# Sheet1.net
KiCad netlist of a schematic drawn in Altium Designer
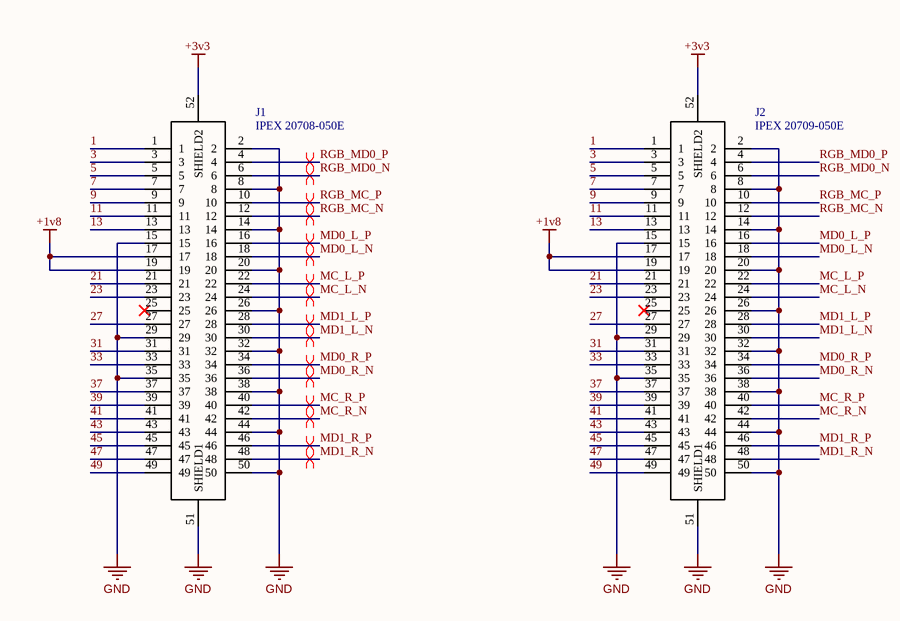
[diagram p0: Sheet1.SchDoc]

(export (version "E")
  (design (tool "Eeschema 10.0.6"))
  (components
    (comp (ref "J1")
      (value "IPEX 20708-050E")
      (footprint "IPEX_20708-050E-01")
      (description "50-Pin Plug. Mates with 20709-050E.")
      (libsource (lib "Schlib1") (part "NOVASTACK 35-P 50 Pin Plug"))
    )
    (comp (ref "J2")
      (value "IPEX 20709-050E")
      (footprint "IPEX_20709-050E-01_20709-050E-01(Primary)")
      (description "50-Pin Plug. Mates with 20708-050E.")
      (libsource (lib "Schlib1") (part "NOVASTACK 35-P 50 Pin Receptical"))
    )
  )
  (nets
    (net (code "1") (name "+1v8") (class "Default")
      (node (ref "J1") (pin "17") (pinfunction "17_17") (pintype "passive"))
      (node (ref "J1") (pin "19") (pinfunction "19_19") (pintype "passive"))
      (node (ref "J2") (pin "17") (pinfunction "17_17") (pintype "passive"))
      (node (ref "J2") (pin "19") (pinfunction "19_19") (pintype "passive"))
    )
    (net (code "2") (name "+3v3") (class "Default")
      (node (ref "J1") (pin "52") (pinfunction "SHIELD2_52") (pintype "passive"))
      (node (ref "J2") (pin "52") (pinfunction "SHIELD2_52") (pintype "passive"))
    )
    (net (code "3") (name "/1") (class "Default")
      (node (ref "J1") (pin "1") (pinfunction "1_1") (pintype "passive"))
      (node (ref "J2") (pin "1") (pinfunction "1_1") (pintype "passive"))
    )
    (net (code "4") (name "/3") (class "Default")
      (node (ref "J1") (pin "3") (pinfunction "3_3") (pintype "passive"))
      (node (ref "J2") (pin "3") (pinfunction "3_3") (pintype "passive"))
    )
    (net (code "5") (name "/5") (class "Default")
      (node (ref "J1") (pin "5") (pinfunction "5_5") (pintype "passive"))
      (node (ref "J2") (pin "5") (pinfunction "5_5") (pintype "passive"))
    )
    (net (code "6") (name "/7") (class "Default")
      (node (ref "J1") (pin "7") (pinfunction "7_7") (pintype "passive"))
      (node (ref "J2") (pin "7") (pinfunction "7_7") (pintype "passive"))
    )
    (net (code "7") (name "/9") (class "Default")
      (node (ref "J1") (pin "9") (pinfunction "9_9") (pintype "passive"))
      (node (ref "J2") (pin "9") (pinfunction "9_9") (pintype "passive"))
    )
    (net (code "8") (name "/11") (class "Default")
      (node (ref "J1") (pin "11") (pinfunction "11_11") (pintype "passive"))
      (node (ref "J2") (pin "11") (pinfunction "11_11") (pintype "passive"))
    )
    (net (code "9") (name "/13") (class "Default")
      (node (ref "J1") (pin "13") (pinfunction "13_13") (pintype "passive"))
      (node (ref "J2") (pin "13") (pinfunction "13_13") (pintype "passive"))
    )
    (net (code "10") (name "/21") (class "Default")
      (node (ref "J1") (pin "21") (pinfunction "21_21") (pintype "passive"))
      (node (ref "J2") (pin "21") (pinfunction "21_21") (pintype "passive"))
    )
    (net (code "11") (name "/23") (class "Default")
      (node (ref "J1") (pin "23") (pinfunction "23_23") (pintype "passive"))
      (node (ref "J2") (pin "23") (pinfunction "23_23") (pintype "passive"))
    )
    (net (code "12") (name "/27") (class "Default")
      (node (ref "J1") (pin "27") (pinfunction "27_27") (pintype "passive"))
      (node (ref "J2") (pin "27") (pinfunction "27_27") (pintype "passive"))
    )
    (net (code "13") (name "/31") (class "Default")
      (node (ref "J1") (pin "31") (pinfunction "31_31") (pintype "passive"))
      (node (ref "J2") (pin "31") (pinfunction "31_31") (pintype "passive"))
    )
    (net (code "14") (name "/33") (class "Default")
      (node (ref "J1") (pin "33") (pinfunction "33_33") (pintype "passive"))
      (node (ref "J2") (pin "33") (pinfunction "33_33") (pintype "passive"))
    )
    (net (code "15") (name "/37") (class "Default")
      (node (ref "J1") (pin "37") (pinfunction "37_37") (pintype "passive"))
      (node (ref "J2") (pin "37") (pinfunction "37_37") (pintype "passive"))
    )
    (net (code "16") (name "/39") (class "Default")
      (node (ref "J1") (pin "39") (pinfunction "39_39") (pintype "passive"))
      (node (ref "J2") (pin "39") (pinfunction "39_39") (pintype "passive"))
    )
    (net (code "17") (name "/41") (class "Default")
      (node (ref "J1") (pin "41") (pinfunction "41_41") (pintype "passive"))
      (node (ref "J2") (pin "41") (pinfunction "41_41") (pintype "passive"))
    )
    (net (code "18") (name "/43") (class "Default")
      (node (ref "J1") (pin "43") (pinfunction "43_43") (pintype "passive"))
      (node (ref "J2") (pin "43") (pinfunction "43_43") (pintype "passive"))
    )
    (net (code "19") (name "/45") (class "Default")
      (node (ref "J1") (pin "45") (pinfunction "45_45") (pintype "passive"))
      (node (ref "J2") (pin "45") (pinfunction "45_45") (pintype "passive"))
    )
    (net (code "20") (name "/47") (class "Default")
      (node (ref "J1") (pin "47") (pinfunction "47_47") (pintype "passive"))
      (node (ref "J2") (pin "47") (pinfunction "47_47") (pintype "passive"))
    )
    (net (code "21") (name "/49") (class "Default")
      (node (ref "J1") (pin "49") (pinfunction "49_49") (pintype "passive"))
      (node (ref "J2") (pin "49") (pinfunction "49_49") (pintype "passive"))
    )
    (net (code "22") (name "/MC_L_N") (class "Default")
      (node (ref "J1") (pin "24") (pinfunction "24_24") (pintype "passive"))
      (node (ref "J2") (pin "24") (pinfunction "24_24") (pintype "passive"))
    )
    (net (code "23") (name "/MC_L_P") (class "Default")
      (node (ref "J1") (pin "22") (pinfunction "22_22") (pintype "passive"))
      (node (ref "J2") (pin "22") (pinfunction "22_22") (pintype "passive"))
    )
    (net (code "24") (name "/MC_R_N") (class "Default")
      (node (ref "J1") (pin "42") (pinfunction "42_42") (pintype "passive"))
      (node (ref "J2") (pin "42") (pinfunction "42_42") (pintype "passive"))
    )
    (net (code "25") (name "/MC_R_P") (class "Default")
      (node (ref "J1") (pin "40") (pinfunction "40_40") (pintype "passive"))
      (node (ref "J2") (pin "40") (pinfunction "40_40") (pintype "passive"))
    )
    (net (code "26") (name "/MD0_L_N") (class "Default")
      (node (ref "J1") (pin "18") (pinfunction "18_18") (pintype "passive"))
      (node (ref "J2") (pin "18") (pinfunction "18_18") (pintype "passive"))
    )
    (net (code "27") (name "/MD0_L_P") (class "Default")
      (node (ref "J1") (pin "16") (pinfunction "16_16") (pintype "passive"))
      (node (ref "J2") (pin "16") (pinfunction "16_16") (pintype "passive"))
    )
    (net (code "28") (name "/MD0_R_N") (class "Default")
      (node (ref "J1") (pin "36") (pinfunction "36_36") (pintype "passive"))
      (node (ref "J2") (pin "36") (pinfunction "36_36") (pintype "passive"))
    )
    (net (code "29") (name "/MD0_R_P") (class "Default")
      (node (ref "J1") (pin "34") (pinfunction "34_34") (pintype "passive"))
      (node (ref "J2") (pin "34") (pinfunction "34_34") (pintype "passive"))
    )
    (net (code "30") (name "/MD1_L_N") (class "Default")
      (node (ref "J1") (pin "30") (pinfunction "30_30") (pintype "passive"))
      (node (ref "J2") (pin "30") (pinfunction "30_30") (pintype "passive"))
    )
    (net (code "31") (name "/MD1_L_P") (class "Default")
      (node (ref "J1") (pin "28") (pinfunction "28_28") (pintype "passive"))
      (node (ref "J2") (pin "28") (pinfunction "28_28") (pintype "passive"))
    )
    (net (code "32") (name "/MD1_R_N") (class "Default")
      (node (ref "J1") (pin "48") (pinfunction "48_48") (pintype "passive"))
      (node (ref "J2") (pin "48") (pinfunction "48_48") (pintype "passive"))
    )
    (net (code "33") (name "/MD1_R_P") (class "Default")
      (node (ref "J1") (pin "46") (pinfunction "46_46") (pintype "passive"))
      (node (ref "J2") (pin "46") (pinfunction "46_46") (pintype "passive"))
    )
    (net (code "34") (name "/RGB_MC_N") (class "Default")
      (node (ref "J1") (pin "12") (pinfunction "12_12") (pintype "passive"))
      (node (ref "J2") (pin "12") (pinfunction "12_12") (pintype "passive"))
    )
    (net (code "35") (name "/RGB_MC_P") (class "Default")
      (node (ref "J1") (pin "10") (pinfunction "10_10") (pintype "passive"))
      (node (ref "J2") (pin "10") (pinfunction "10_10") (pintype "passive"))
    )
    (net (code "36") (name "/RGB_MD0_N") (class "Default")
      (node (ref "J1") (pin "6") (pinfunction "6_6") (pintype "passive"))
      (node (ref "J2") (pin "6") (pinfunction "6_6") (pintype "passive"))
    )
    (net (code "37") (name "/RGB_MD0_P") (class "Default")
      (node (ref "J1") (pin "4") (pinfunction "4_4") (pintype "passive"))
      (node (ref "J2") (pin "4") (pinfunction "4_4") (pintype "passive"))
    )
    (net (code "38") (name "GND") (class "Default")
      (node (ref "J1") (pin "14") (pinfunction "14_14") (pintype "passive"))
      (node (ref "J1") (pin "15") (pinfunction "15_15") (pintype "passive"))
      (node (ref "J1") (pin "2") (pinfunction "2_2") (pintype "passive"))
      (node (ref "J1") (pin "20") (pinfunction "20_20") (pintype "passive"))
      (node (ref "J1") (pin "26") (pinfunction "26_26") (pintype "passive"))
      (node (ref "J1") (pin "29") (pinfunction "29_29") (pintype "passive"))
      (node (ref "J1") (pin "32") (pinfunction "32_32") (pintype "passive"))
      (node (ref "J1") (pin "35") (pinfunction "35_35") (pintype "passive"))
      (node (ref "J1") (pin "38") (pinfunction "38_38") (pintype "passive"))
      (node (ref "J1") (pin "44") (pinfunction "44_44") (pintype "passive"))
      (node (ref "J1") (pin "50") (pinfunction "50_50") (pintype "passive"))
      (node (ref "J1") (pin "51") (pinfunction "SHIELD1_51") (pintype "passive"))
      (node (ref "J1") (pin "8") (pinfunction "8_8") (pintype "passive"))
      (node (ref "J2") (pin "14") (pinfunction "14_14") (pintype "passive"))
      (node (ref "J2") (pin "15") (pinfunction "15_15") (pintype "passive"))
      (node (ref "J2") (pin "2") (pinfunction "2_2") (pintype "passive"))
      (node (ref "J2") (pin "20") (pinfunction "20_20") (pintype "passive"))
      (node (ref "J2") (pin "26") (pinfunction "26_26") (pintype "passive"))
      (node (ref "J2") (pin "29") (pinfunction "29_29") (pintype "passive"))
      (node (ref "J2") (pin "32") (pinfunction "32_32") (pintype "passive"))
      (node (ref "J2") (pin "35") (pinfunction "35_35") (pintype "passive"))
      (node (ref "J2") (pin "38") (pinfunction "38_38") (pintype "passive"))
      (node (ref "J2") (pin "44") (pinfunction "44_44") (pintype "passive"))
      (node (ref "J2") (pin "50") (pinfunction "50_50") (pintype "passive"))
      (node (ref "J2") (pin "51") (pinfunction "SHIELD1_51") (pintype "passive"))
      (node (ref "J2") (pin "8") (pinfunction "8_8") (pintype "passive"))
    )
    (net (code "39") (name "unconnected-(J1-Pad25)") (class "Default")
      (node (ref "J1") (pin "25") (pinfunction "25_25") (pintype "passive+no_connect"))
    )
    (net (code "40") (name "unconnected-(J2-Pad25)") (class "Default")
      (node (ref "J2") (pin "25") (pinfunction "25_25") (pintype "passive+no_connect"))
    )
  )
)
